# mega2560.net
KiCad netlist of a schematic drawn in Altium Designer
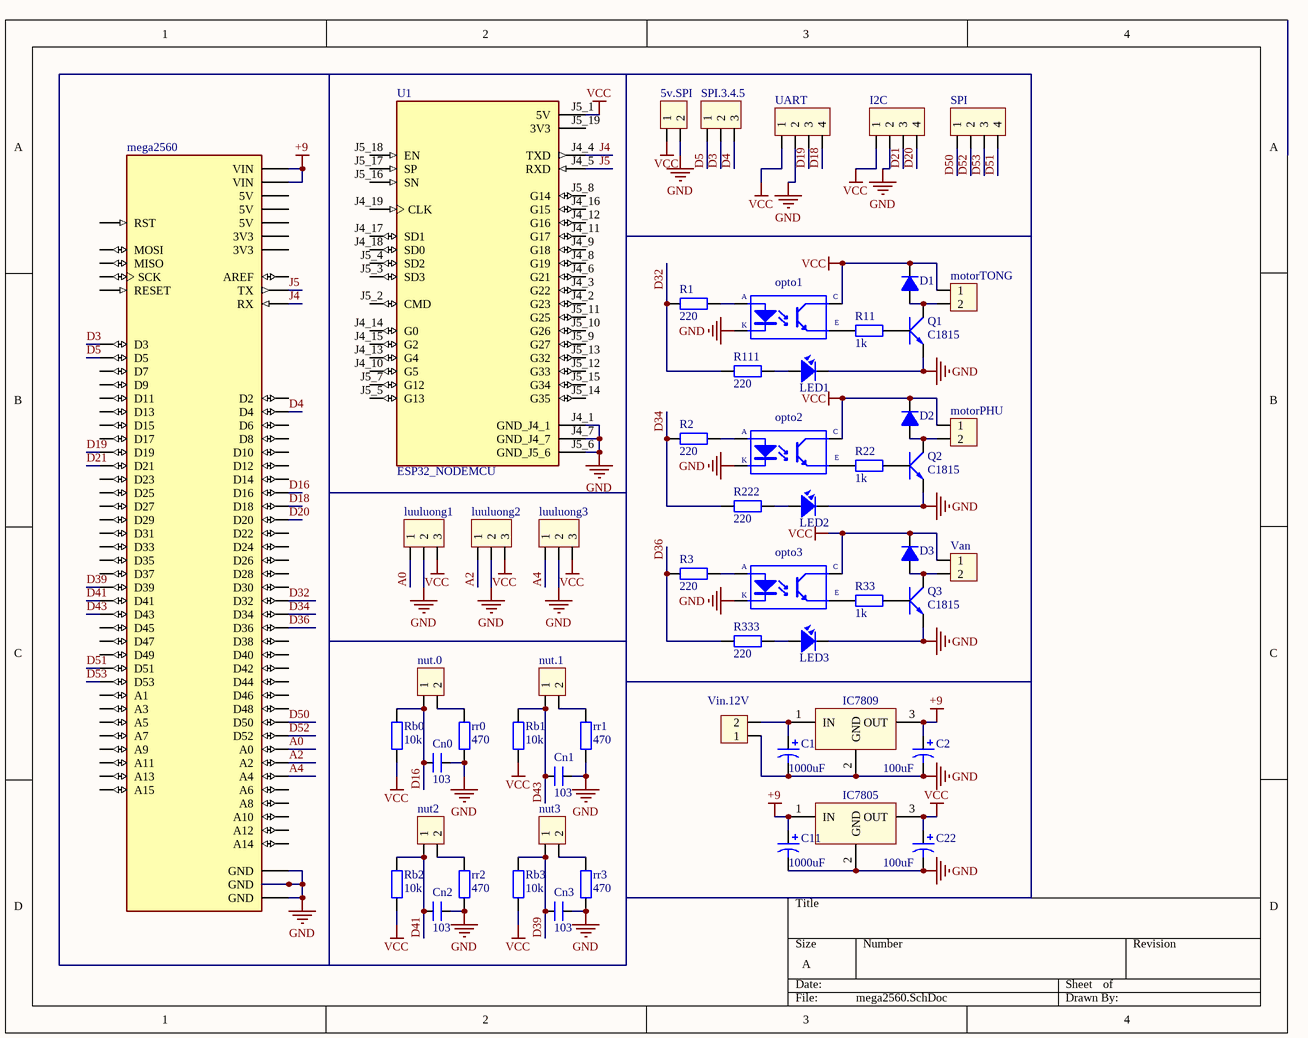
[diagram p0: mega2560.SchDoc]

(export (version "E")
  (design (tool "Eeschema 10.0.6"))
  (components
    (comp (ref "5v.SPI")
      (value "~")
      (footprint "HED2")
      (description "Header 2 (Green)")
      (libsource (lib "syhaunguyen") (part "Hed2"))
    )
    (comp (ref "C1")
      (value "1000uF")
      (footprint "CP2/5")
      (description "Polarized Capacitor (Surface Mount)")
      (fields (field (name "PUBLISHER") "Altium Limited"))
      (libsource (lib "syhaunguyen") (part "Cap Pol3"))
    )
    (comp (ref "C2")
      (value "100uF")
      (footprint "CP2/5")
      (description "Polarized Capacitor (Surface Mount)")
      (fields (field (name "PUBLISHER") "Altium Limited"))
      (libsource (lib "syhaunguyen") (part "Cap Pol3"))
    )
    (comp (ref "C11")
      (value "1000uF")
      (footprint "CP2/5")
      (description "Polarized Capacitor (Surface Mount)")
      (fields (field (name "PUBLISHER") "Altium Limited"))
      (libsource (lib "syhaunguyen") (part "Cap Pol3"))
    )
    (comp (ref "C22")
      (value "100uF")
      (footprint "CP2/5")
      (description "Polarized Capacitor (Surface Mount)")
      (fields (field (name "PUBLISHER") "Altium Limited"))
      (libsource (lib "syhaunguyen") (part "Cap Pol3"))
    )
    (comp (ref "Cn0")
      (value "103")
      (footprint "CN1.5")
      (description "Cap np 682pF => 104pF")
      (libsource (lib "syhaunguyen") (part "CN1.5"))
    )
    (comp (ref "Cn1")
      (value "103")
      (footprint "CN1.5")
      (description "Cap np 682pF => 104pF")
      (libsource (lib "syhaunguyen") (part "CN1.5"))
    )
    (comp (ref "Cn2")
      (value "103")
      (footprint "CN1.5")
      (description "Cap np 682pF => 104pF")
      (libsource (lib "syhaunguyen") (part "CN1.5"))
    )
    (comp (ref "Cn3")
      (value "103")
      (footprint "CN1.5")
      (description "Cap np 682pF => 104pF")
      (libsource (lib "syhaunguyen") (part "CN1.5"))
    )
    (comp (ref "D1")
      (value "~")
      (footprint "D5A")
      (description "Diode 5A")
      (libsource (lib "syhaunguyen") (part "D5A"))
    )
    (comp (ref "D2")
      (value "~")
      (footprint "D5A")
      (description "Diode 5A")
      (libsource (lib "syhaunguyen") (part "D5A"))
    )
    (comp (ref "D3")
      (value "~")
      (footprint "D5A")
      (description "Diode 5A")
      (libsource (lib "syhaunguyen") (part "D5A"))
    )
    (comp (ref "I2C")
      (value "~")
      (footprint "HED4")
      (description "Header 4 (Green)")
      (libsource (lib "syhaunguyen") (part "Hed4"))
    )
    (comp (ref "IC7805")
      (value "~")
      (footprint "QTO-220")
      (description "On ap +, from + 5 to + 24VDC")
      (libsource (lib "syhaunguyen") (part "LM78xx"))
    )
    (comp (ref "IC7809")
      (value "~")
      (footprint "QTO-220")
      (description "On ap +, from + 5 to + 24VDC")
      (libsource (lib "syhaunguyen") (part "LM78xx"))
    )
    (comp (ref "LED1")
      (value "LED")
      (footprint "LED-3")
      (description "LED Single colour Green and Red")
      (libsource (lib "syhaunguyen") (part "LED"))
    )
    (comp (ref "LED2")
      (value "LED")
      (footprint "LED-3")
      (description "LED Single colour Green and Red")
      (libsource (lib "syhaunguyen") (part "LED"))
    )
    (comp (ref "LED3")
      (value "LED")
      (footprint "LED-3")
      (description "LED Single colour Green and Red")
      (libsource (lib "syhaunguyen") (part "LED"))
    )
    (comp (ref "luuluong1")
      (value "~")
      (footprint "HED3")
      (description "Header 3 (Green)")
      (libsource (lib "syhaunguyen") (part "Hed3"))
    )
    (comp (ref "luuluong2")
      (value "~")
      (footprint "HED3")
      (description "Header 3 (Green)")
      (libsource (lib "syhaunguyen") (part "Hed3"))
    )
    (comp (ref "luuluong3")
      (value "~")
      (footprint "HED3")
      (description "Header 3 (Green)")
      (libsource (lib "syhaunguyen") (part "Hed3"))
    )
    (comp (ref "mega2560")
      (value "~")
      (footprint "MODULE_MEGA_PRO_EMBED_CH340G_/_ATMEGA2560")
      (description "Mega 2560 PRO (Embed) CH340G/ATmega2560-16AU")
      (fields (field (name "MP") "MEGA_PRO_EMBED_CH340G_/_ATMEGA2560"))
      (libsource (lib "MEGA_PRO_EMBED_CH340G___ATMEGA2560") (part "MEGA_PRO_EMBED_CH340G_/_ATMEGA2560"))
    )
    (comp (ref "motorPHU")
      (value "~")
      (footprint "HED2")
      (description "Header 2 (Green)")
      (libsource (lib "") (part "Hed2_2"))
    )
    (comp (ref "motorTONG")
      (value "~")
      (footprint "HED2")
      (description "Header 2 (Green)")
      (libsource (lib "") (part "Hed2_2"))
    )
    (comp (ref "nut.0")
      (value "~")
      (footprint "HED2")
      (description "Header 2 (Green)")
      (libsource (lib "syhaunguyen") (part "Hed2"))
    )
    (comp (ref "nut.1")
      (value "~")
      (footprint "HED2")
      (description "Header 2 (Green)")
      (libsource (lib "syhaunguyen") (part "Hed2"))
    )
    (comp (ref "nut2")
      (value "~")
      (footprint "HED2")
      (description "Header 2 (Green)")
      (libsource (lib "syhaunguyen") (part "Hed2"))
    )
    (comp (ref "nut3")
      (value "~")
      (footprint "HED2")
      (description "Header 2 (Green)")
      (libsource (lib "syhaunguyen") (part "Hed2"))
    )
    (comp (ref "opto1")
      (value "~")
      (footprint "OPTO_U")
      (description "Single Opto")
      (libsource (lib "syhaunguyen") (part "OPTO_U"))
    )
    (comp (ref "opto2")
      (value "~")
      (footprint "OPTO_U")
      (description "Single Opto")
      (libsource (lib "syhaunguyen") (part "OPTO_U"))
    )
    (comp (ref "opto3")
      (value "~")
      (footprint "OPTO_U")
      (description "Single Opto")
      (libsource (lib "syhaunguyen") (part "OPTO_U"))
    )
    (comp (ref "Q1")
      (value "C1815")
      (footprint "QTO-92")
      (description "NPN 600mW, ECB")
      (libsource (lib "syhaunguyen") (part "C1815"))
    )
    (comp (ref "Q2")
      (value "C1815")
      (footprint "QTO-92")
      (description "NPN 600mW, ECB")
      (libsource (lib "syhaunguyen") (part "C1815"))
    )
    (comp (ref "Q3")
      (value "C1815")
      (footprint "QTO-92")
      (description "NPN 600mW, ECB")
      (libsource (lib "syhaunguyen") (part "C1815"))
    )
    (comp (ref "R1")
      (value "220")
      (footprint "R1/4W")
      (description "Resistor 1/4W")
      (libsource (lib "syhaunguyen") (part "R1/4W"))
    )
    (comp (ref "R2")
      (value "220")
      (footprint "R1/4W")
      (description "Resistor 1/4W")
      (libsource (lib "syhaunguyen") (part "R1/4W"))
    )
    (comp (ref "R3")
      (value "220")
      (footprint "R1/4W")
      (description "Resistor 1/4W")
      (libsource (lib "syhaunguyen") (part "R1/4W"))
    )
    (comp (ref "R11")
      (value "1k")
      (footprint "R1/4W")
      (description "Resistor 1/4W")
      (libsource (lib "syhaunguyen") (part "R1/4W"))
    )
    (comp (ref "R22")
      (value "1k")
      (footprint "R1/4W")
      (description "Resistor 1/4W")
      (libsource (lib "syhaunguyen") (part "R1/4W"))
    )
    (comp (ref "R33")
      (value "1k")
      (footprint "R1/4W")
      (description "Resistor 1/4W")
      (libsource (lib "syhaunguyen") (part "R1/4W"))
    )
    (comp (ref "R111")
      (value "220")
      (footprint "R1/4W")
      (description "Resistor 1/4W")
      (libsource (lib "syhaunguyen") (part "R1/4W"))
    )
    (comp (ref "R222")
      (value "220")
      (footprint "R1/4W")
      (description "Resistor 1/4W")
      (libsource (lib "syhaunguyen") (part "R1/4W"))
    )
    (comp (ref "R333")
      (value "220")
      (footprint "R1/4W")
      (description "Resistor 1/4W")
      (libsource (lib "syhaunguyen") (part "R1/4W"))
    )
    (comp (ref "Rb0")
      (value "10k")
      (footprint "R1/4W")
      (description "Resistor 1/4W")
      (libsource (lib "syhaunguyen") (part "R1/4W"))
    )
    (comp (ref "Rb1")
      (value "10k")
      (footprint "R1/4W")
      (description "Resistor 1/4W")
      (libsource (lib "syhaunguyen") (part "R1/4W"))
    )
    (comp (ref "Rb2")
      (value "10k")
      (footprint "R1/4W")
      (description "Resistor 1/4W")
      (libsource (lib "syhaunguyen") (part "R1/4W"))
    )
    (comp (ref "Rb3")
      (value "10k")
      (footprint "R1/4W")
      (description "Resistor 1/4W")
      (libsource (lib "syhaunguyen") (part "R1/4W"))
    )
    (comp (ref "rr0")
      (value "470")
      (footprint "R1/4W")
      (description "Resistor 1/4W")
      (libsource (lib "syhaunguyen") (part "R1/4W"))
    )
    (comp (ref "rr1")
      (value "470")
      (footprint "R1/4W")
      (description "Resistor 1/4W")
      (libsource (lib "syhaunguyen") (part "R1/4W"))
    )
    (comp (ref "rr2")
      (value "470")
      (footprint "R1/4W")
      (description "Resistor 1/4W")
      (libsource (lib "syhaunguyen") (part "R1/4W"))
    )
    (comp (ref "rr3")
      (value "470")
      (footprint "R1/4W")
      (description "Resistor 1/4W")
      (libsource (lib "syhaunguyen") (part "R1/4W"))
    )
    (comp (ref "SPI")
      (value "~")
      (footprint "HED4")
      (description "Header 4 (Green)")
      (libsource (lib "syhaunguyen") (part "Hed4"))
    )
    (comp (ref "SPI.3.4.5")
      (value "~")
      (footprint "HED3")
      (description "Header 3 (Green)")
      (libsource (lib "syhaunguyen") (part "Hed3"))
    )
    (comp (ref "U1")
      (value "ESP32_NODEMCU")
      (footprint "MODULE_ESP32_NODEMCU")
      (fields (field (name "MF") "Espressif Systems") (field (name "MP") "ESP32 NODEMCU"))
      (libsource (lib "ESP32_NODEMCU") (part "ESP32_NODEMCU"))
    )
    (comp (ref "UART")
      (value "~")
      (footprint "HED4")
      (description "Header 4 (Green)")
      (libsource (lib "syhaunguyen") (part "Hed4"))
    )
    (comp (ref "Van")
      (value "~")
      (footprint "HED2")
      (description "Header 2 (Green)")
      (libsource (lib "") (part "Hed2_2"))
    )
    (comp (ref "Vin.12V")
      (value "~")
      (footprint "HED2")
      (description "Header 2 (Green)")
      (libsource (lib "") (part "Hed2_1"))
    )
  )
  (nets
    (net (code "1") (name "+9") (class "Default")
      (node (ref "C11") (pin "1") (pinfunction "1_1") (pintype "passive"))
      (node (ref "C2") (pin "1") (pinfunction "1_1") (pintype "passive"))
      (node (ref "IC7805") (pin "1") (pinfunction "IN_1") (pintype "passive"))
      (node (ref "IC7809") (pin "3") (pinfunction "OUT_3") (pintype "passive"))
      (node (ref "mega2560") (pin "VIN_1") (pinfunction "VIN_VIN_1") (pintype "power_in"))
      (node (ref "mega2560") (pin "VIN_2") (pinfunction "VIN_VIN_2") (pintype "power_in"))
    )
    (net (code "2") (name "/A0") (class "Default")
      (node (ref "luuluong1") (pin "1") (pinfunction "1_1") (pintype "passive"))
      (node (ref "mega2560") (pin "A0") (pinfunction "A0_A0") (pintype "bidirectional"))
    )
    (net (code "3") (name "/A2") (class "Default")
      (node (ref "luuluong2") (pin "1") (pinfunction "1_1") (pintype "passive"))
      (node (ref "mega2560") (pin "A2") (pinfunction "A2_A2") (pintype "bidirectional"))
    )
    (net (code "4") (name "/A4") (class "Default")
      (node (ref "luuluong3") (pin "1") (pinfunction "1_1") (pintype "passive"))
      (node (ref "mega2560") (pin "A4") (pinfunction "A4_A4") (pintype "bidirectional"))
    )
    (net (code "5") (name "/D3") (class "Default")
      (node (ref "SPI.3.4.5") (pin "2") (pinfunction "2_2") (pintype "passive"))
      (node (ref "mega2560") (pin "D3") (pinfunction "D3_D3") (pintype "bidirectional"))
    )
    (net (code "6") (name "/D4") (class "Default")
      (node (ref "SPI.3.4.5") (pin "3") (pinfunction "3_3") (pintype "passive"))
      (node (ref "mega2560") (pin "D4") (pinfunction "D4_D4") (pintype "bidirectional"))
    )
    (net (code "7") (name "/D5") (class "Default")
      (node (ref "SPI.3.4.5") (pin "1") (pinfunction "1_1") (pintype "passive"))
      (node (ref "mega2560") (pin "D5") (pinfunction "D5_D5") (pintype "bidirectional"))
    )
    (net (code "8") (name "/D16") (class "Default")
      (node (ref "Cn0") (pin "2") (pinfunction "2_2") (pintype "passive"))
      (node (ref "Rb0") (pin "1") (pinfunction "1_1") (pintype "passive"))
      (node (ref "mega2560") (pin "D16") (pinfunction "D16_D16") (pintype "bidirectional"))
      (node (ref "nut.0") (pin "1") (pinfunction "1_1") (pintype "passive"))
    )
    (net (code "9") (name "/D18") (class "Default")
      (node (ref "UART") (pin "4") (pinfunction "4_4") (pintype "passive"))
      (node (ref "mega2560") (pin "D18") (pinfunction "D18_D18") (pintype "bidirectional"))
    )
    (net (code "10") (name "/D19") (class "Default")
      (node (ref "UART") (pin "3") (pinfunction "3_3") (pintype "passive"))
      (node (ref "mega2560") (pin "D19") (pinfunction "D19_D19") (pintype "bidirectional"))
    )
    (net (code "11") (name "/D20") (class "Default")
      (node (ref "I2C") (pin "4") (pinfunction "4_4") (pintype "passive"))
      (node (ref "mega2560") (pin "D20") (pinfunction "D20_D20") (pintype "bidirectional"))
    )
    (net (code "12") (name "/D21") (class "Default")
      (node (ref "I2C") (pin "3") (pinfunction "3_3") (pintype "passive"))
      (node (ref "mega2560") (pin "D21") (pinfunction "D21_D21") (pintype "bidirectional"))
    )
    (net (code "13") (name "/D32") (class "Default")
      (node (ref "R1") (pin "1") (pinfunction "1_1") (pintype "passive"))
      (node (ref "R111") (pin "1") (pinfunction "1_1") (pintype "passive"))
      (node (ref "mega2560") (pin "D32") (pinfunction "D32_D32") (pintype "bidirectional"))
    )
    (net (code "14") (name "/D34") (class "Default")
      (node (ref "R2") (pin "1") (pinfunction "1_1") (pintype "passive"))
      (node (ref "R222") (pin "1") (pinfunction "1_1") (pintype "passive"))
      (node (ref "mega2560") (pin "D34") (pinfunction "D34_D34") (pintype "bidirectional"))
    )
    (net (code "15") (name "/D36") (class "Default")
      (node (ref "R3") (pin "2") (pinfunction "2_2") (pintype "passive"))
      (node (ref "R333") (pin "1") (pinfunction "1_1") (pintype "passive"))
      (node (ref "mega2560") (pin "D36") (pinfunction "D36_D36") (pintype "bidirectional"))
    )
    (net (code "16") (name "/D39") (class "Default")
      (node (ref "Cn3") (pin "2") (pinfunction "2_2") (pintype "passive"))
      (node (ref "Rb3") (pin "1") (pinfunction "1_1") (pintype "passive"))
      (node (ref "mega2560") (pin "D39") (pinfunction "D39_D39") (pintype "bidirectional"))
      (node (ref "nut3") (pin "1") (pinfunction "1_1") (pintype "passive"))
    )
    (net (code "17") (name "/D41") (class "Default")
      (node (ref "Cn2") (pin "2") (pinfunction "2_2") (pintype "passive"))
      (node (ref "Rb2") (pin "1") (pinfunction "1_1") (pintype "passive"))
      (node (ref "mega2560") (pin "D41") (pinfunction "D41_D41") (pintype "bidirectional"))
      (node (ref "nut2") (pin "1") (pinfunction "1_1") (pintype "passive"))
    )
    (net (code "18") (name "/D43") (class "Default")
      (node (ref "Cn1") (pin "2") (pinfunction "2_2") (pintype "passive"))
      (node (ref "Rb1") (pin "1") (pinfunction "1_1") (pintype "passive"))
      (node (ref "mega2560") (pin "D43") (pinfunction "D43_D43") (pintype "bidirectional"))
      (node (ref "nut.1") (pin "1") (pinfunction "1_1") (pintype "passive"))
    )
    (net (code "19") (name "/D50") (class "Default")
      (node (ref "SPI") (pin "1") (pinfunction "1_1") (pintype "passive"))
      (node (ref "mega2560") (pin "D50") (pinfunction "D50_D50") (pintype "bidirectional"))
    )
    (net (code "20") (name "/D51") (class "Default")
      (node (ref "SPI") (pin "4") (pinfunction "4_4") (pintype "passive"))
      (node (ref "mega2560") (pin "D51") (pinfunction "D51_D51") (pintype "bidirectional"))
    )
    (net (code "21") (name "/D52") (class "Default")
      (node (ref "SPI") (pin "2") (pinfunction "2_2") (pintype "passive"))
      (node (ref "mega2560") (pin "D52") (pinfunction "D52_D52") (pintype "bidirectional"))
    )
    (net (code "22") (name "/D53") (class "Default")
      (node (ref "SPI") (pin "3") (pinfunction "3_3") (pintype "passive"))
      (node (ref "mega2560") (pin "D53") (pinfunction "D53_D53") (pintype "bidirectional"))
    )
    (net (code "23") (name "/J4") (class "Default")
      (node (ref "U1") (pin "J4_4") (pinfunction "TXD_J4_4") (pintype "output"))
      (node (ref "mega2560") (pin "RX") (pinfunction "RX_RX") (pintype "input"))
    )
    (net (code "24") (name "/J5") (class "Default")
      (node (ref "U1") (pin "J4_5") (pinfunction "RXD_J4_5") (pintype "input"))
      (node (ref "mega2560") (pin "TX") (pinfunction "TX_TX") (pintype "output"))
    )
    (net (code "25") (name "GND") (class "Default")
      (node (ref "5v.SPI") (pin "2") (pinfunction "2_2") (pintype "passive"))
      (node (ref "C1") (pin "2") (pinfunction "2_2") (pintype "passive"))
      (node (ref "C11") (pin "2") (pinfunction "2_2") (pintype "passive"))
      (node (ref "C2") (pin "2") (pinfunction "2_2") (pintype "passive"))
      (node (ref "C22") (pin "2") (pinfunction "2_2") (pintype "passive"))
      (node (ref "Cn0") (pin "1") (pinfunction "1_1") (pintype "passive"))
      (node (ref "Cn1") (pin "1") (pinfunction "1_1") (pintype "passive"))
      (node (ref "Cn2") (pin "1") (pinfunction "1_1") (pintype "passive"))
      (node (ref "Cn3") (pin "1") (pinfunction "1_1") (pintype "passive"))
      (node (ref "I2C") (pin "2") (pinfunction "2_2") (pintype "passive"))
      (node (ref "IC7805") (pin "2") (pinfunction "GND_2") (pintype "passive"))
      (node (ref "IC7809") (pin "2") (pinfunction "GND_2") (pintype "passive"))
      (node (ref "LED1") (pin "2") (pinfunction "2_2") (pintype "passive"))
      (node (ref "LED2") (pin "2") (pinfunction "2_2") (pintype "passive"))
      (node (ref "LED3") (pin "2") (pinfunction "2_2") (pintype "passive"))
      (node (ref "Q1") (pin "1") (pinfunction "E_1") (pintype "passive"))
      (node (ref "Q2") (pin "1") (pinfunction "E_1") (pintype "passive"))
      (node (ref "Q3") (pin "1") (pinfunction "E_1") (pintype "passive"))
      (node (ref "U1") (pin "J4_1") (pinfunction "GND_J4_1_J4_1") (pintype "power_in"))
      (node (ref "U1") (pin "J4_7") (pinfunction "GND_J4_7_J4_7") (pintype "power_in"))
      (node (ref "U1") (pin "J5_6") (pinfunction "GND_J5_6_J5_6") (pintype "power_in"))
      (node (ref "UART") (pin "2") (pinfunction "2_2") (pintype "passive"))
      (node (ref "Vin.12V") (pin "1") (pinfunction "1_1") (pintype "passive"))
      (node (ref "luuluong1") (pin "2") (pinfunction "2_2") (pintype "passive"))
      (node (ref "luuluong2") (pin "2") (pinfunction "2_2") (pintype "passive"))
      (node (ref "luuluong3") (pin "2") (pinfunction "2_2") (pintype "passive"))
      (node (ref "mega2560") (pin "GND_1") (pinfunction "GND_GND_1") (pintype "power_in"))
      (node (ref "mega2560") (pin "GND_2") (pinfunction "GND_GND_2") (pintype "power_in"))
      (node (ref "mega2560") (pin "GND_3") (pinfunction "GND_GND_3") (pintype "power_in"))
      (node (ref "opto1") (pin "K") (pinfunction "K_K") (pintype "passive"))
      (node (ref "opto2") (pin "K") (pinfunction "K_K") (pintype "passive"))
      (node (ref "opto3") (pin "K") (pinfunction "K_K") (pintype "passive"))
      (node (ref "rr0") (pin "2") (pinfunction "2_2") (pintype "passive"))
      (node (ref "rr1") (pin "2") (pinfunction "2_2") (pintype "passive"))
      (node (ref "rr2") (pin "2") (pinfunction "2_2") (pintype "passive"))
      (node (ref "rr3") (pin "2") (pinfunction "2_2") (pintype "passive"))
    )
    (net (code "26") (name "Net-(D1-A)") (class "Default")
      (node (ref "D1") (pin "1") (pinfunction "A_1") (pintype "passive"))
      (node (ref "Q1") (pin "2") (pinfunction "C_2") (pintype "passive"))
      (node (ref "motorTONG") (pin "2") (pinfunction "2_2") (pintype "passive"))
    )
    (net (code "27") (name "Net-(D2-A)") (class "Default")
      (node (ref "D2") (pin "1") (pinfunction "A_1") (pintype "passive"))
      (node (ref "Q2") (pin "2") (pinfunction "C_2") (pintype "passive"))
      (node (ref "motorPHU") (pin "2") (pinfunction "2_2") (pintype "passive"))
    )
    (net (code "28") (name "Net-(D3-A)") (class "Default")
      (node (ref "D3") (pin "1") (pinfunction "A_1") (pintype "passive"))
      (node (ref "Q3") (pin "2") (pinfunction "C_2") (pintype "passive"))
      (node (ref "Van") (pin "2") (pinfunction "2_2") (pintype "passive"))
    )
    (net (code "29") (name "Net-(IC7809-IN)") (class "Default")
      (node (ref "C1") (pin "1") (pinfunction "1_1") (pintype "passive"))
      (node (ref "IC7809") (pin "1") (pinfunction "IN_1") (pintype "passive"))
      (node (ref "Vin.12V") (pin "2") (pinfunction "2_2") (pintype "passive"))
    )
    (net (code "30") (name "Net-(LED1-Pad1)") (class "Default")
      (node (ref "LED1") (pin "1") (pinfunction "1_1") (pintype "passive"))
      (node (ref "R111") (pin "2") (pinfunction "2_2") (pintype "passive"))
    )
    (net (code "31") (name "Net-(LED2-Pad1)") (class "Default")
      (node (ref "LED2") (pin "1") (pinfunction "1_1") (pintype "passive"))
      (node (ref "R222") (pin "2") (pinfunction "2_2") (pintype "passive"))
    )
    (net (code "32") (name "Net-(LED3-Pad1)") (class "Default")
      (node (ref "LED3") (pin "1") (pinfunction "1_1") (pintype "passive"))
      (node (ref "R333") (pin "2") (pinfunction "2_2") (pintype "passive"))
    )
    (net (code "33") (name "Net-(Q1-B)") (class "Default")
      (node (ref "Q1") (pin "3") (pinfunction "B_3") (pintype "passive"))
      (node (ref "R11") (pin "2") (pinfunction "2_2") (pintype "passive"))
    )
    (net (code "34") (name "Net-(Q2-B)") (class "Default")
      (node (ref "Q2") (pin "3") (pinfunction "B_3") (pintype "passive"))
      (node (ref "R22") (pin "2") (pinfunction "2_2") (pintype "passive"))
    )
    (net (code "35") (name "Net-(Q3-B)") (class "Default")
      (node (ref "Q3") (pin "3") (pinfunction "B_3") (pintype "passive"))
      (node (ref "R33") (pin "2") (pinfunction "2_2") (pintype "passive"))
    )
    (net (code "36") (name "Net-(R1-Pad2)") (class "Default")
      (node (ref "R1") (pin "2") (pinfunction "2_2") (pintype "passive"))
      (node (ref "opto1") (pin "A") (pinfunction "A_A") (pintype "passive"))
    )
    (net (code "37") (name "Net-(R2-Pad2)") (class "Default")
      (node (ref "R2") (pin "2") (pinfunction "2_2") (pintype "passive"))
      (node (ref "opto2") (pin "A") (pinfunction "A_A") (pintype "passive"))
    )
    (net (code "38") (name "Net-(R3-Pad1)") (class "Default")
      (node (ref "R3") (pin "1") (pinfunction "1_1") (pintype "passive"))
      (node (ref "opto3") (pin "A") (pinfunction "A_A") (pintype "passive"))
    )
    (net (code "39") (name "Net-(R11-Pad1)") (class "Default")
      (node (ref "R11") (pin "1") (pinfunction "1_1") (pintype "passive"))
      (node (ref "opto1") (pin "E") (pinfunction "E_E") (pintype "passive"))
    )
    (net (code "40") (name "Net-(R22-Pad1)") (class "Default")
      (node (ref "R22") (pin "1") (pinfunction "1_1") (pintype "passive"))
      (node (ref "opto2") (pin "E") (pinfunction "E_E") (pintype "passive"))
    )
    (net (code "41") (name "Net-(R33-Pad1)") (class "Default")
      (node (ref "R33") (pin "1") (pinfunction "1_1") (pintype "passive"))
      (node (ref "opto3") (pin "E") (pinfunction "E_E") (pintype "passive"))
    )
    (net (code "42") (name "Net-(nut.0-Pad2)") (class "Default")
      (node (ref "nut.0") (pin "2") (pinfunction "2_2") (pintype "passive"))
      (node (ref "rr0") (pin "1") (pinfunction "1_1") (pintype "passive"))
    )
    (net (code "43") (name "Net-(nut.1-Pad2)") (class "Default")
      (node (ref "nut.1") (pin "2") (pinfunction "2_2") (pintype "passive"))
      (node (ref "rr1") (pin "1") (pinfunction "1_1") (pintype "passive"))
    )
    (net (code "44") (name "Net-(nut2-Pad2)") (class "Default")
      (node (ref "nut2") (pin "2") (pinfunction "2_2") (pintype "passive"))
      (node (ref "rr2") (pin "1") (pinfunction "1_1") (pintype "passive"))
    )
    (net (code "45") (name "Net-(nut3-Pad2)") (class "Default")
      (node (ref "nut3") (pin "2") (pinfunction "2_2") (pintype "passive"))
      (node (ref "rr3") (pin "1") (pinfunction "1_1") (pintype "passive"))
    )
    (net (code "46") (name "VCC") (class "Default")
      (node (ref "5v.SPI") (pin "1") (pinfunction "1_1") (pintype "passive"))
      (node (ref "C22") (pin "1") (pinfunction "1_1") (pintype "passive"))
      (node (ref "D1") (pin "2") (pinfunction "K_2") (pintype "passive"))
      (node (ref "D2") (pin "2") (pinfunction "K_2") (pintype "passive"))
      (node (ref "D3") (pin "2") (pinfunction "K_2") (pintype "passive"))
      (node (ref "I2C") (pin "1") (pinfunction "1_1") (pintype "passive"))
      (node (ref "IC7805") (pin "3") (pinfunction "OUT_3") (pintype "passive"))
      (node (ref "Rb0") (pin "2") (pinfunction "2_2") (pintype "passive"))
      (node (ref "Rb1") (pin "2") (pinfunction "2_2") (pintype "passive"))
      (node (ref "Rb2") (pin "2") (pinfunction "2_2") (pintype "passive"))
      (node (ref "Rb3") (pin "2") (pinfunction "2_2") (pintype "passive"))
      (node (ref "U1") (pin "J5_1") (pinfunction "5V_J5_1") (pintype "power_in"))
      (node (ref "UART") (pin "1") (pinfunction "1_1") (pintype "passive"))
      (node (ref "Van") (pin "1") (pinfunction "1_1") (pintype "passive"))
      (node (ref "luuluong1") (pin "3") (pinfunction "3_3") (pintype "passive"))
      (node (ref "luuluong2") (pin "3") (pinfunction "3_3") (pintype "passive"))
      (node (ref "luuluong3") (pin "3") (pinfunction "3_3") (pintype "passive"))
      (node (ref "motorPHU") (pin "1") (pinfunction "1_1") (pintype "passive"))
      (node (ref "motorTONG") (pin "1") (pinfunction "1_1") (pintype "passive"))
      (node (ref "opto1") (pin "C") (pinfunction "C_C") (pintype "passive"))
      (node (ref "opto2") (pin "C") (pinfunction "C_C") (pintype "passive"))
      (node (ref "opto3") (pin "C") (pinfunction "C_C") (pintype "passive"))
    )
    (net (code "47") (name "unconnected-(U1-3V3-PadJ5_19)") (class "Default")
      (node (ref "U1") (pin "J5_19") (pinfunction "3V3_J5_19") (pintype "power_in"))
    )
    (net (code "48") (name "unconnected-(U1-CLK-PadJ4_19)") (class "Default")
      (node (ref "U1") (pin "J4_19") (pinfunction "CLK_J4_19") (pintype "input"))
    )
    (net (code "49") (name "unconnected-(U1-CMD-PadJ5_2)") (class "Default")
      (node (ref "U1") (pin "J5_2") (pinfunction "CMD_J5_2") (pintype "bidirectional"))
    )
    (net (code "50") (name "unconnected-(U1-EN-PadJ5_18)") (class "Default")
      (node (ref "U1") (pin "J5_18") (pinfunction "EN_J5_18") (pintype "input"))
    )
    (net (code "51") (name "unconnected-(U1-G0-PadJ4_14)") (class "Default")
      (node (ref "U1") (pin "J4_14") (pinfunction "G0_J4_14") (pintype "bidirectional"))
    )
    (net (code "52") (name "unconnected-(U1-G2-PadJ4_15)") (class "Default")
      (node (ref "U1") (pin "J4_15") (pinfunction "G2_J4_15") (pintype "bidirectional"))
    )
    (net (code "53") (name "unconnected-(U1-G4-PadJ4_13)") (class "Default")
      (node (ref "U1") (pin "J4_13") (pinfunction "G4_J4_13") (pintype "bidirectional"))
    )
    (net (code "54") (name "unconnected-(U1-G5-PadJ4_10)") (class "Default")
      (node (ref "U1") (pin "J4_10") (pinfunction "G5_J4_10") (pintype "bidirectional"))
    )
    (net (code "55") (name "unconnected-(U1-G12-PadJ5_7)") (class "Default")
      (node (ref "U1") (pin "J5_7") (pinfunction "G12_J5_7") (pintype "bidirectional"))
    )
    (net (code "56") (name "unconnected-(U1-G13-PadJ5_5)") (class "Default")
      (node (ref "U1") (pin "J5_5") (pinfunction "G13_J5_5") (pintype "bidirectional"))
    )
    (net (code "57") (name "unconnected-(U1-G14-PadJ5_8)") (class "Default")
      (node (ref "U1") (pin "J5_8") (pinfunction "G14_J5_8") (pintype "bidirectional"))
    )
    (net (code "58") (name "unconnected-(U1-G15-PadJ4_16)") (class "Default")
      (node (ref "U1") (pin "J4_16") (pinfunction "G15_J4_16") (pintype "bidirectional"))
    )
    (net (code "59") (name "unconnected-(U1-G16-PadJ4_12)") (class "Default")
      (node (ref "U1") (pin "J4_12") (pinfunction "G16_J4_12") (pintype "bidirectional"))
    )
    (net (code "60") (name "unconnected-(U1-G17-PadJ4_11)") (class "Default")
      (node (ref "U1") (pin "J4_11") (pinfunction "G17_J4_11") (pintype "bidirectional"))
    )
    (net (code "61") (name "unconnected-(U1-G18-PadJ4_9)") (class "Default")
      (node (ref "U1") (pin "J4_9") (pinfunction "G18_J4_9") (pintype "bidirectional"))
    )
    (net (code "62") (name "unconnected-(U1-G19-PadJ4_8)") (class "Default")
      (node (ref "U1") (pin "J4_8") (pinfunction "G19_J4_8") (pintype "bidirectional"))
    )
    (net (code "63") (name "unconnected-(U1-G21-PadJ4_6)") (class "Default")
      (node (ref "U1") (pin "J4_6") (pinfunction "G21_J4_6") (pintype "bidirectional"))
    )
    (net (code "64") (name "unconnected-(U1-G22-PadJ4_3)") (class "Default")
      (node (ref "U1") (pin "J4_3") (pinfunction "G22_J4_3") (pintype "bidirectional"))
    )
    (net (code "65") (name "unconnected-(U1-G23-PadJ4_2)") (class "Default")
      (node (ref "U1") (pin "J4_2") (pinfunction "G23_J4_2") (pintype "bidirectional"))
    )
    (net (code "66") (name "unconnected-(U1-G25-PadJ5_11)") (class "Default")
      (node (ref "U1") (pin "J5_11") (pinfunction "G25_J5_11") (pintype "bidirectional"))
    )
    (net (code "67") (name "unconnected-(U1-G26-PadJ5_10)") (class "Default")
      (node (ref "U1") (pin "J5_10") (pinfunction "G26_J5_10") (pintype "bidirectional"))
    )
    (net (code "68") (name "unconnected-(U1-G27-PadJ5_9)") (class "Default")
      (node (ref "U1") (pin "J5_9") (pinfunction "G27_J5_9") (pintype "bidirectional"))
    )
    (net (code "69") (name "unconnected-(U1-G32-PadJ5_13)") (class "Default")
      (node (ref "U1") (pin "J5_13") (pinfunction "G32_J5_13") (pintype "bidirectional"))
    )
    (net (code "70") (name "unconnected-(U1-G33-PadJ5_12)") (class "Default")
      (node (ref "U1") (pin "J5_12") (pinfunction "G33_J5_12") (pintype "bidirectional"))
    )
    (net (code "71") (name "unconnected-(U1-G34-PadJ5_15)") (class "Default")
      (node (ref "U1") (pin "J5_15") (pinfunction "G34_J5_15") (pintype "bidirectional"))
    )
    (net (code "72") (name "unconnected-(U1-G35-PadJ5_14)") (class "Default")
      (node (ref "U1") (pin "J5_14") (pinfunction "G35_J5_14") (pintype "bidirectional"))
    )
    (net (code "73") (name "unconnected-(U1-SD0-PadJ4_18)") (class "Default")
      (node (ref "U1") (pin "J4_18") (pinfunction "SD0_J4_18") (pintype "bidirectional"))
    )
    (net (code "74") (name "unconnected-(U1-SD1-PadJ4_17)") (class "Default")
      (node (ref "U1") (pin "J4_17") (pinfunction "SD1_J4_17") (pintype "bidirectional"))
    )
    (net (code "75") (name "unconnected-(U1-SD2-PadJ5_4)") (class "Default")
      (node (ref "U1") (pin "J5_4") (pinfunction "SD2_J5_4") (pintype "bidirectional"))
    )
    (net (code "76") (name "unconnected-(U1-SD3-PadJ5_3)") (class "Default")
      (node (ref "U1") (pin "J5_3") (pinfunction "SD3_J5_3") (pintype "bidirectional"))
    )
    (net (code "77") (name "unconnected-(U1-SN-PadJ5_16)") (class "Default")
      (node (ref "U1") (pin "J5_16") (pinfunction "SN_J5_16") (pintype "input"))
    )
    (net (code "78") (name "unconnected-(U1-SP-PadJ5_17)") (class "Default")
      (node (ref "U1") (pin "J5_17") (pinfunction "SP_J5_17") (pintype "input"))
    )
    (net (code "79") (name "unconnected-(mega2560-3V3-Pad3V3_1)") (class "Default")
      (node (ref "mega2560") (pin "3V3_1") (pinfunction "3V3_3V3_1") (pintype "power_in"))
    )
    (net (code "80") (name "unconnected-(mega2560-3V3-Pad3V3_2)") (class "Default")
      (node (ref "mega2560") (pin "3V3_2") (pinfunction "3V3_3V3_2") (pintype "power_in"))
    )
    (net (code "81") (name "unconnected-(mega2560-5V-Pad5V_1)") (class "Default")
      (node (ref "mega2560") (pin "5V_1") (pinfunction "5V_5V_1") (pintype "power_in"))
    )
    (net (code "82") (name "unconnected-(mega2560-5V-Pad5V_2)") (class "Default")
      (node (ref "mega2560") (pin "5V_2") (pinfunction "5V_5V_2") (pintype "power_in"))
    )
    (net (code "83") (name "unconnected-(mega2560-5V-Pad5V_3)") (class "Default")
      (node (ref "mega2560") (pin "5V_3") (pinfunction "5V_5V_3") (pintype "power_in"))
    )
    (net (code "84") (name "unconnected-(mega2560-PadA1)") (class "Default")
      (node (ref "mega2560") (pin "A1") (pinfunction "A1_A1") (pintype "bidirectional"))
    )
    (net (code "85") (name "unconnected-(mega2560-PadA3)") (class "Default")
      (node (ref "mega2560") (pin "A3") (pinfunction "A3_A3") (pintype "bidirectional"))
    )
    (net (code "86") (name "unconnected-(mega2560-PadA5)") (class "Default")
      (node (ref "mega2560") (pin "A5") (pinfunction "A5_A5") (pintype "bidirectional"))
    )
    (net (code "87") (name "unconnected-(mega2560-PadA6)") (class "Default")
      (node (ref "mega2560") (pin "A6") (pinfunction "A6_A6") (pintype "bidirectional"))
    )
    (net (code "88") (name "unconnected-(mega2560-PadA7)") (class "Default")
      (node (ref "mega2560") (pin "A7") (pinfunction "A7_A7") (pintype "bidirectional"))
    )
    (net (code "89") (name "unconnected-(mega2560-PadA8)") (class "Default")
      (node (ref "mega2560") (pin "A8") (pinfunction "A8_A8") (pintype "bidirectional"))
    )
    (net (code "90") (name "unconnected-(mega2560-PadA9)") (class "Default")
      (node (ref "mega2560") (pin "A9") (pinfunction "A9_A9") (pintype "bidirectional"))
    )
    (net (code "91") (name "unconnected-(mega2560-PadA10)") (class "Default")
      (node (ref "mega2560") (pin "A10") (pinfunction "A10_A10") (pintype "bidirectional"))
    )
    (net (code "92") (name "unconnected-(mega2560-PadA11)") (class "Default")
      (node (ref "mega2560") (pin "A11") (pinfunction "A11_A11") (pintype "bidirectional"))
    )
    (net (code "93") (name "unconnected-(mega2560-PadA12)") (class "Default")
      (node (ref "mega2560") (pin "A12") (pinfunction "A12_A12") (pintype "bidirectional"))
    )
    (net (code "94") (name "unconnected-(mega2560-PadA13)") (class "Default")
      (node (ref "mega2560") (pin "A13") (pinfunction "A13_A13") (pintype "bidirectional"))
    )
    (net (code "95") (name "unconnected-(mega2560-PadA14)") (class "Default")
      (node (ref "mega2560") (pin "A14") (pinfunction "A14_A14") (pintype "bidirectional"))
    )
    (net (code "96") (name "unconnected-(mega2560-PadA15)") (class "Default")
      (node (ref "mega2560") (pin "A15") (pinfunction "A15_A15") (pintype "bidirectional"))
    )
    (net (code "97") (name "unconnected-(mega2560-PadAREF)") (class "Default")
      (node (ref "mega2560") (pin "AREF") (pinfunction "AREF_AREF") (pintype "bidirectional"))
    )
    (net (code "98") (name "unconnected-(mega2560-PadD2)") (class "Default")
      (node (ref "mega2560") (pin "D2") (pinfunction "D2_D2") (pintype "bidirectional"))
    )
    (net (code "99") (name "unconnected-(mega2560-PadD6)") (class "Default")
      (node (ref "mega2560") (pin "D6") (pinfunction "D6_D6") (pintype "bidirectional"))
    )
    (net (code "100") (name "unconnected-(mega2560-PadD7)") (class "Default")
      (node (ref "mega2560") (pin "D7") (pinfunction "D7_D7") (pintype "bidirectional"))
    )
    (net (code "101") (name "unconnected-(mega2560-PadD8)") (class "Default")
      (node (ref "mega2560") (pin "D8") (pinfunction "D8_D8") (pintype "bidirectional"))
    )
    (net (code "102") (name "unconnected-(mega2560-PadD9)") (class "Default")
      (node (ref "mega2560") (pin "D9") (pinfunction "D9_D9") (pintype "bidirectional"))
    )
    (net (code "103") (name "unconnected-(mega2560-PadD10)") (class "Default")
      (node (ref "mega2560") (pin "D10") (pinfunction "D10_D10") (pintype "bidirectional"))
    )
    (net (code "104") (name "unconnected-(mega2560-PadD11)") (class "Default")
      (node (ref "mega2560") (pin "D11") (pinfunction "D11_D11") (pintype "bidirectional"))
    )
    (net (code "105") (name "unconnected-(mega2560-PadD12)") (class "Default")
      (node (ref "mega2560") (pin "D12") (pinfunction "D12_D12") (pintype "bidirectional"))
    )
    (net (code "106") (name "unconnected-(mega2560-PadD13)") (class "Default")
      (node (ref "mega2560") (pin "D13") (pinfunction "D13_D13") (pintype "bidirectional"))
    )
    (net (code "107") (name "unconnected-(mega2560-PadD14)") (class "Default")
      (node (ref "mega2560") (pin "D14") (pinfunction "D14_D14") (pintype "bidirectional"))
    )
    (net (code "108") (name "unconnected-(mega2560-PadD15)") (class "Default")
      (node (ref "mega2560") (pin "D15") (pinfunction "D15_D15") (pintype "bidirectional"))
    )
    (net (code "109") (name "unconnected-(mega2560-PadD17)") (class "Default")
      (node (ref "mega2560") (pin "D17") (pinfunction "D17_D17") (pintype "bidirectional"))
    )
    (net (code "110") (name "unconnected-(mega2560-PadD22)") (class "Default")
      (node (ref "mega2560") (pin "D22") (pinfunction "D22_D22") (pintype "bidirectional"))
    )
    (net (code "111") (name "unconnected-(mega2560-PadD23)") (class "Default")
      (node (ref "mega2560") (pin "D23") (pinfunction "D23_D23") (pintype "bidirectional"))
    )
    (net (code "112") (name "unconnected-(mega2560-PadD24)") (class "Default")
      (node (ref "mega2560") (pin "D24") (pinfunction "D24_D24") (pintype "bidirectional"))
    )
    (net (code "113") (name "unconnected-(mega2560-PadD25)") (class "Default")
      (node (ref "mega2560") (pin "D25") (pinfunction "D25_D25") (pintype "bidirectional"))
    )
    (net (code "114") (name "unconnected-(mega2560-PadD26)") (class "Default")
      (node (ref "mega2560") (pin "D26") (pinfunction "D26_D26") (pintype "bidirectional"))
    )
    (net (code "115") (name "unconnected-(mega2560-PadD27)") (class "Default")
      (node (ref "mega2560") (pin "D27") (pinfunction "D27_D27") (pintype "bidirectional"))
    )
    (net (code "116") (name "unconnected-(mega2560-PadD28)") (class "Default")
      (node (ref "mega2560") (pin "D28") (pinfunction "D28_D28") (pintype "bidirectional"))
    )
    (net (code "117") (name "unconnected-(mega2560-PadD29)") (class "Default")
      (node (ref "mega2560") (pin "D29") (pinfunction "D29_D29") (pintype "bidirectional"))
    )
    (net (code "118") (name "unconnected-(mega2560-PadD30)") (class "Default")
      (node (ref "mega2560") (pin "D30") (pinfunction "D30_D30") (pintype "bidirectional"))
    )
    (net (code "119") (name "unconnected-(mega2560-PadD31)") (class "Default")
      (node (ref "mega2560") (pin "D31") (pinfunction "D31_D31") (pintype "bidirectional"))
    )
    (net (code "120") (name "unconnected-(mega2560-PadD33)") (class "Default")
      (node (ref "mega2560") (pin "D33") (pinfunction "D33_D33") (pintype "bidirectional"))
    )
    (net (code "121") (name "unconnected-(mega2560-PadD35)") (class "Default")
      (node (ref "mega2560") (pin "D35") (pinfunction "D35_D35") (pintype "bidirectional"))
    )
    (net (code "122") (name "unconnected-(mega2560-PadD37)") (class "Default")
      (node (ref "mega2560") (pin "D37") (pinfunction "D37_D37") (pintype "bidirectional"))
    )
    (net (code "123") (name "unconnected-(mega2560-PadD38)") (class "Default")
      (node (ref "mega2560") (pin "D38") (pinfunction "D38_D38") (pintype "bidirectional"))
    )
    (net (code "124") (name "unconnected-(mega2560-PadD40)") (class "Default")
      (node (ref "mega2560") (pin "D40") (pinfunction "D40_D40") (pintype "bidirectional"))
    )
    (net (code "125") (name "unconnected-(mega2560-PadD42)") (class "Default")
      (node (ref "mega2560") (pin "D42") (pinfunction "D42_D42") (pintype "bidirectional"))
    )
    (net (code "126") (name "unconnected-(mega2560-PadD44)") (class "Default")
      (node (ref "mega2560") (pin "D44") (pinfunction "D44_D44") (pintype "bidirectional"))
    )
    (net (code "127") (name "unconnected-(mega2560-PadD45)") (class "Default")
      (node (ref "mega2560") (pin "D45") (pinfunction "D45_D45") (pintype "bidirectional"))
    )
    (net (code "128") (name "unconnected-(mega2560-PadD46)") (class "Default")
      (node (ref "mega2560") (pin "D46") (pinfunction "D46_D46") (pintype "bidirectional"))
    )
    (net (code "129") (name "unconnected-(mega2560-PadD47)") (class "Default")
      (node (ref "mega2560") (pin "D47") (pinfunction "D47_D47") (pintype "bidirectional"))
    )
    (net (code "130") (name "unconnected-(mega2560-PadD48)") (class "Default")
      (node (ref "mega2560") (pin "D48") (pinfunction "D48_D48") (pintype "bidirectional"))
    )
    (net (code "131") (name "unconnected-(mega2560-PadD49)") (class "Default")
      (node (ref "mega2560") (pin "D49") (pinfunction "D49_D49") (pintype "bidirectional"))
    )
    (net (code "132") (name "unconnected-(mega2560-PadMISO)") (class "Default")
      (node (ref "mega2560") (pin "MISO") (pinfunction "MISO_MISO") (pintype "bidirectional"))
    )
    (net (code "133") (name "unconnected-(mega2560-PadMOSI)") (class "Default")
      (node (ref "mega2560") (pin "MOSI") (pinfunction "MOSI_MOSI") (pintype "bidirectional"))
    )
    (net (code "134") (name "unconnected-(mega2560-PadRESET)") (class "Default")
      (node (ref "mega2560") (pin "RESET") (pinfunction "RESET_RESET") (pintype "input"))
    )
    (net (code "135") (name "unconnected-(mega2560-PadRST)") (class "Default")
      (node (ref "mega2560") (pin "RST") (pinfunction "RST_RST") (pintype "input"))
    )
    (net (code "136") (name "unconnected-(mega2560-PadSCK)") (class "Default")
      (node (ref "mega2560") (pin "SCK") (pinfunction "SCK_SCK") (pintype "bidirectional"))
    )
  )
)
